# MORPH_RECONPLAT.net
KiCad netlist of a schematic drawn in EAGLE
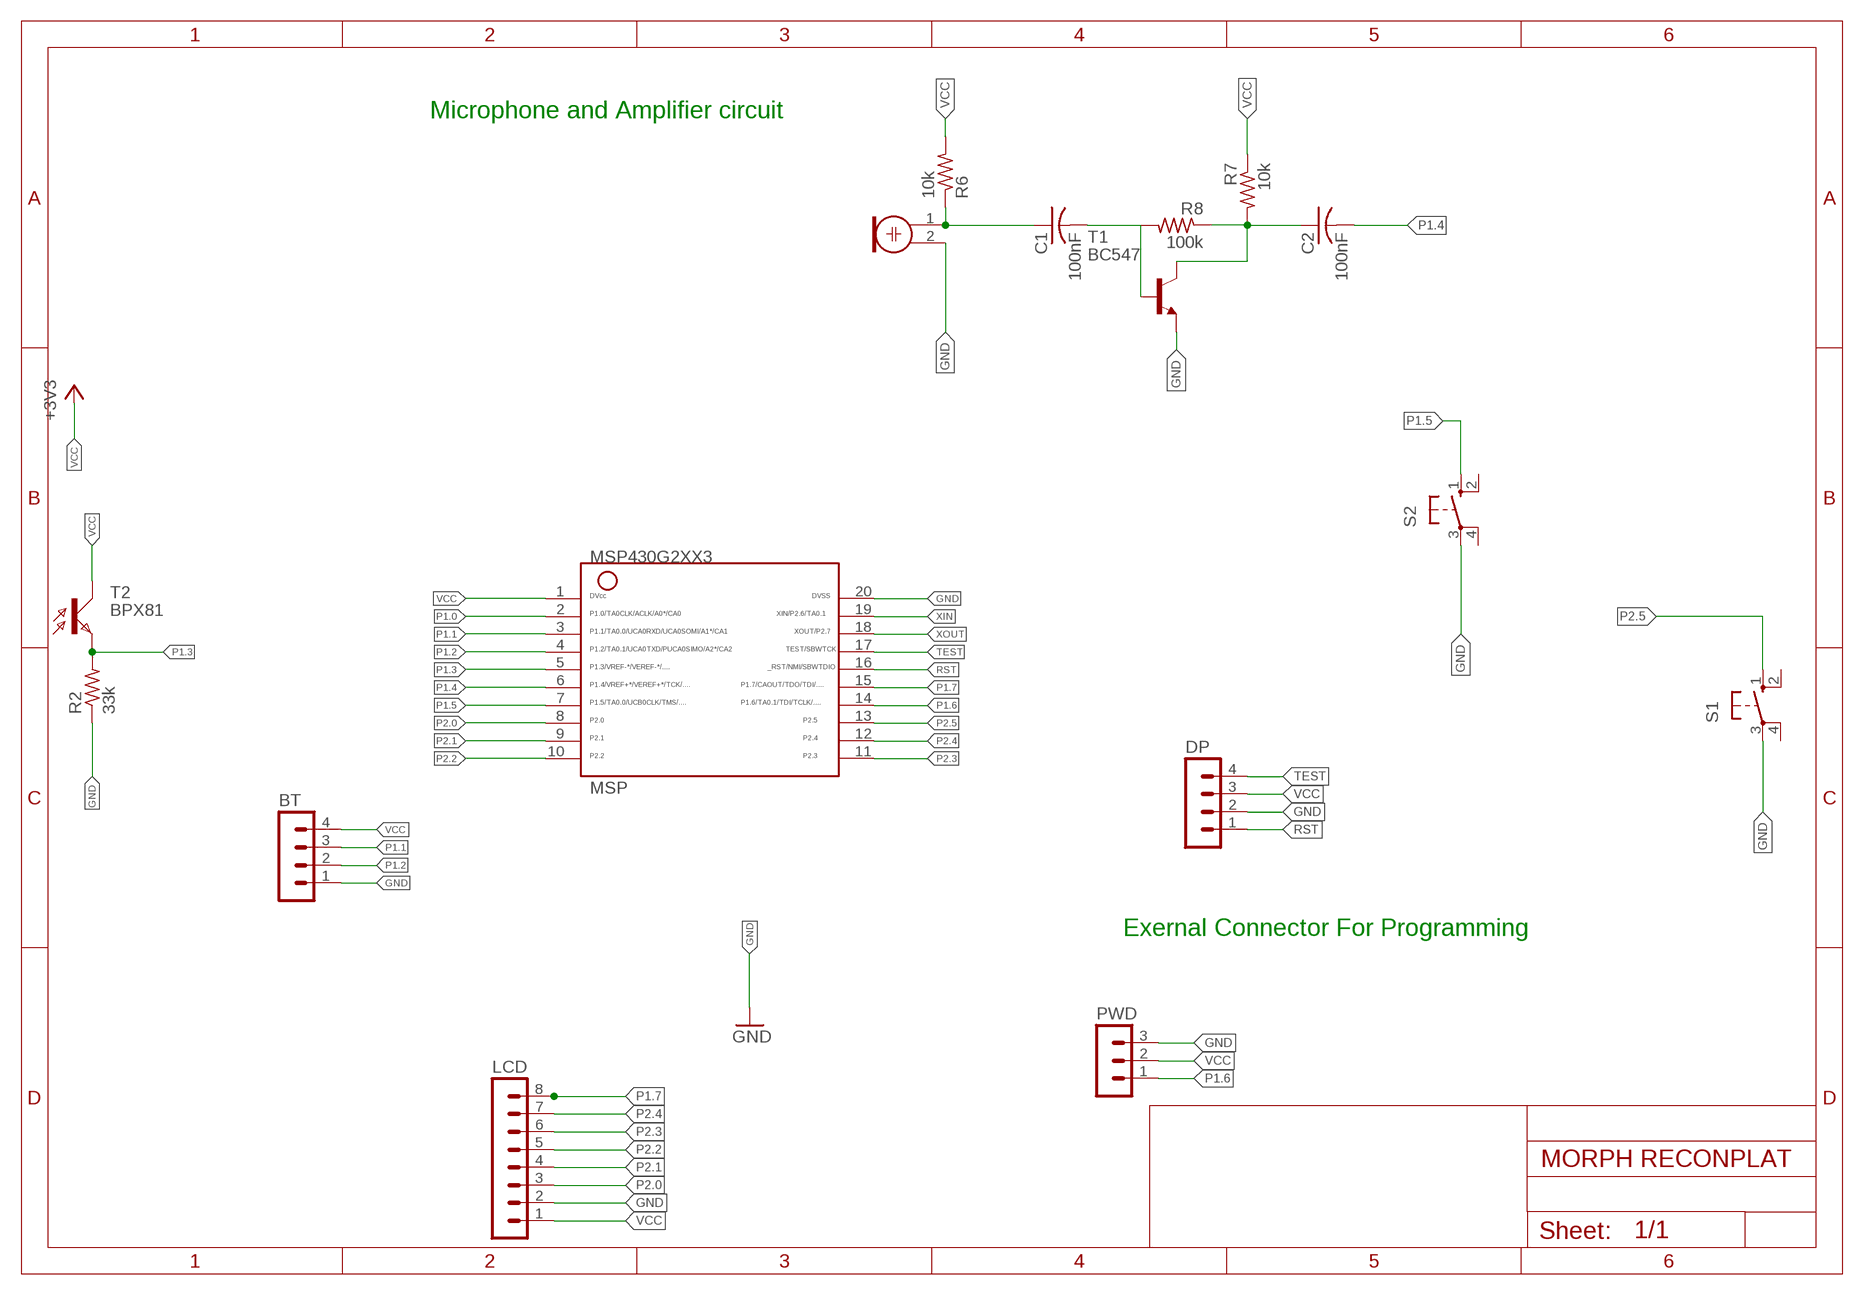
[diagram p0: schematic, sheet 1]

(export (version "E")
  (design (tool "Eeschema 10.0.6"))
  (components
    (comp (ref "BT")
      (value "MA04-1")
      (footprint "eagle-import:MA04-1")
      (libsource (lib "eagle-import") (part "MA04-1"))
    )
    (comp (ref "C1")
      (value "100nF")
      (footprint "eagle-import:C025-025X050")
      (libsource (lib "eagle-import") (part "C-US025-025X050"))
    )
    (comp (ref "C2")
      (value "100nF")
      (footprint "eagle-import:C025-025X050")
      (libsource (lib "eagle-import") (part "C-US025-025X050"))
    )
    (comp (ref "DP")
      (value "MA04-1")
      (footprint "eagle-import:MA04-1")
      (libsource (lib "eagle-import") (part "MA04-1"))
    )
    (comp (ref "LCD")
      (value "MA08-1")
      (footprint "eagle-import:MA08-1")
      (libsource (lib "eagle-import") (part "MA08-1"))
    )
    (comp (ref "M1")
      (value "ELECTRET_MICROPHON-WM-64PC/64PK")
      (footprint "eagle-import:WM-64PC_64PK")
      (libsource (lib "eagle-import") (part "ELECTRET_MICROPHON-WM-64PC/64PK"))
    )
    (comp (ref "MSP")
      (value "G2XX3---N20")
      (footprint "eagle-import:N20")
      (libsource (lib "eagle-import") (part "G2XX3---N20"))
    )
    (comp (ref "PWD")
      (value "MA03-1")
      (footprint "eagle-import:MA03-1")
      (libsource (lib "eagle-import") (part "MA03-1"))
    )
    (comp (ref "R2")
      (value "33k")
      (footprint "eagle-import:0207_10")
      (libsource (lib "eagle-import") (part "R-US_0207/10"))
    )
    (comp (ref "R6")
      (value "10k")
      (footprint "eagle-import:0207_10")
      (libsource (lib "eagle-import") (part "R-US_0207/10"))
    )
    (comp (ref "R7")
      (value "10k")
      (footprint "eagle-import:0207_10")
      (libsource (lib "eagle-import") (part "R-US_0207/10"))
    )
    (comp (ref "R8")
      (value "100k")
      (footprint "eagle-import:0207_10")
      (libsource (lib "eagle-import") (part "R-US_0207/10"))
    )
    (comp (ref "S1")
      (value "10-XX")
      (footprint "eagle-import:B3F-10XX")
      (fields (field (name "MPN") "B3F-1000"))
      (libsource (lib "eagle-import") (part "10-XX"))
    )
    (comp (ref "S2")
      (value "10-XX")
      (footprint "eagle-import:B3F-10XX")
      (fields (field (name "MPN") "B3F-1000"))
      (libsource (lib "eagle-import") (part "10-XX"))
    )
    (comp (ref "T1")
      (value "BC547")
      (footprint "eagle-import:TO92")
      (libsource (lib "eagle-import") (part "BC547"))
    )
    (comp (ref "T2")
      (value "BPX81")
      (footprint "eagle-import:BPX81")
      (libsource (lib "eagle-import") (part "BPX81"))
    )
  )
  (nets
    (net (code "1") (name "GND") (class "Default")
      (node (ref "BT") (pin "1") (pinfunction "1_1") (pintype "passive"))
      (node (ref "DP") (pin "2") (pinfunction "2_2") (pintype "passive"))
      (node (ref "LCD") (pin "2") (pinfunction "2_2") (pintype "passive"))
      (node (ref "M1") (pin "2") (pinfunction "2_2") (pintype "passive"))
      (node (ref "MSP") (pin "20") (pinfunction "20_20") (pintype "bidirectional"))
      (node (ref "PWD") (pin "3") (pinfunction "3_3") (pintype "passive"))
      (node (ref "R2") (pin "1") (pinfunction "1_1") (pintype "passive"))
      (node (ref "S1") (pin "3") (pinfunction "P_3") (pintype "passive"))
      (node (ref "S2") (pin "3") (pinfunction "P_3") (pintype "passive"))
      (node (ref "T1") (pin "1") (pinfunction "E_1") (pintype "passive"))
    )
    (net (code "2") (name "Net-(C1-Pad1)") (class "Default")
      (node (ref "C1") (pin "1") (pinfunction "1_1") (pintype "passive"))
      (node (ref "M1") (pin "1") (pinfunction "1_1") (pintype "passive"))
      (node (ref "R6") (pin "1") (pinfunction "1_1") (pintype "passive"))
    )
    (net (code "3") (name "Net-(T1-B)") (class "Default")
      (node (ref "C1") (pin "2") (pinfunction "2_2") (pintype "passive"))
      (node (ref "R8") (pin "2") (pinfunction "2_2") (pintype "passive"))
      (node (ref "T1") (pin "2") (pinfunction "B_2") (pintype "passive"))
    )
    (net (code "4") (name "Net-(T1-C)") (class "Default")
      (node (ref "C2") (pin "1") (pinfunction "1_1") (pintype "passive"))
      (node (ref "R7") (pin "2") (pinfunction "2_2") (pintype "passive"))
      (node (ref "R8") (pin "1") (pinfunction "1_1") (pintype "passive"))
      (node (ref "T1") (pin "3") (pinfunction "C_3") (pintype "passive"))
    )
    (net (code "5") (name "P1.0") (class "Default")
      (node (ref "MSP") (pin "2") (pinfunction "2_2") (pintype "bidirectional"))
    )
    (net (code "6") (name "P1.1") (class "Default")
      (node (ref "BT") (pin "3") (pinfunction "3_3") (pintype "passive"))
      (node (ref "MSP") (pin "3") (pinfunction "3_3") (pintype "bidirectional"))
    )
    (net (code "7") (name "P1.2") (class "Default")
      (node (ref "BT") (pin "2") (pinfunction "2_2") (pintype "passive"))
      (node (ref "MSP") (pin "4") (pinfunction "4_4") (pintype "bidirectional"))
    )
    (net (code "8") (name "P1.3") (class "Default")
      (node (ref "MSP") (pin "5") (pinfunction "5_5") (pintype "bidirectional"))
      (node (ref "R2") (pin "2") (pinfunction "2_2") (pintype "passive"))
      (node (ref "T2") (pin "E") (pinfunction "E_E") (pintype "passive"))
    )
    (net (code "9") (name "P1.4") (class "Default")
      (node (ref "C2") (pin "2") (pinfunction "2_2") (pintype "passive"))
      (node (ref "MSP") (pin "6") (pinfunction "6_6") (pintype "bidirectional"))
    )
    (net (code "10") (name "P1.5") (class "Default")
      (node (ref "MSP") (pin "7") (pinfunction "7_7") (pintype "bidirectional"))
      (node (ref "S2") (pin "1") (pinfunction "S_1") (pintype "passive"))
    )
    (net (code "11") (name "P1.6") (class "Default")
      (node (ref "MSP") (pin "14") (pinfunction "14_14") (pintype "bidirectional"))
      (node (ref "PWD") (pin "1") (pinfunction "1_1") (pintype "passive"))
    )
    (net (code "12") (name "P1.7") (class "Default")
      (node (ref "LCD") (pin "8") (pinfunction "8_8") (pintype "passive"))
      (node (ref "MSP") (pin "15") (pinfunction "15_15") (pintype "bidirectional"))
    )
    (net (code "13") (name "P2.0") (class "Default")
      (node (ref "LCD") (pin "3") (pinfunction "3_3") (pintype "passive"))
      (node (ref "MSP") (pin "8") (pinfunction "8_8") (pintype "bidirectional"))
    )
    (net (code "14") (name "P2.1") (class "Default")
      (node (ref "LCD") (pin "4") (pinfunction "4_4") (pintype "passive"))
      (node (ref "MSP") (pin "9") (pinfunction "9_9") (pintype "bidirectional"))
    )
    (net (code "15") (name "P2.2") (class "Default")
      (node (ref "LCD") (pin "5") (pinfunction "5_5") (pintype "passive"))
      (node (ref "MSP") (pin "10") (pinfunction "10_10") (pintype "bidirectional"))
    )
    (net (code "16") (name "P2.3") (class "Default")
      (node (ref "LCD") (pin "6") (pinfunction "6_6") (pintype "passive"))
      (node (ref "MSP") (pin "11") (pinfunction "11_11") (pintype "bidirectional"))
    )
    (net (code "17") (name "P2.4") (class "Default")
      (node (ref "LCD") (pin "7") (pinfunction "7_7") (pintype "passive"))
      (node (ref "MSP") (pin "12") (pinfunction "12_12") (pintype "bidirectional"))
    )
    (net (code "18") (name "P2.5") (class "Default")
      (node (ref "MSP") (pin "13") (pinfunction "13_13") (pintype "bidirectional"))
      (node (ref "S1") (pin "1") (pinfunction "S_1") (pintype "passive"))
    )
    (net (code "19") (name "RST") (class "Default")
      (node (ref "DP") (pin "1") (pinfunction "1_1") (pintype "passive"))
      (node (ref "MSP") (pin "16") (pinfunction "16_16") (pintype "bidirectional"))
    )
    (net (code "20") (name "TEST") (class "Default")
      (node (ref "DP") (pin "4") (pinfunction "4_4") (pintype "passive"))
      (node (ref "MSP") (pin "17") (pinfunction "17_17") (pintype "bidirectional"))
    )
    (net (code "21") (name "VCC") (class "Default")
      (node (ref "BT") (pin "4") (pinfunction "4_4") (pintype "passive"))
      (node (ref "DP") (pin "3") (pinfunction "3_3") (pintype "passive"))
      (node (ref "LCD") (pin "1") (pinfunction "1_1") (pintype "passive"))
      (node (ref "MSP") (pin "1") (pinfunction "1_1") (pintype "bidirectional"))
      (node (ref "PWD") (pin "2") (pinfunction "2_2") (pintype "passive"))
      (node (ref "R6") (pin "2") (pinfunction "2_2") (pintype "passive"))
      (node (ref "R7") (pin "1") (pinfunction "1_1") (pintype "passive"))
      (node (ref "T2") (pin "C") (pinfunction "C_C") (pintype "passive"))
    )
    (net (code "22") (name "XIN") (class "Default")
      (node (ref "MSP") (pin "19") (pinfunction "19_19") (pintype "bidirectional"))
    )
    (net (code "23") (name "XOUT") (class "Default")
      (node (ref "MSP") (pin "18") (pinfunction "18_18") (pintype "bidirectional"))
    )
    (net (code "24") (name "unconnected-(S1-P1-Pad4)") (class "Default")
      (node (ref "S1") (pin "4") (pinfunction "P1_4") (pintype "passive"))
    )
    (net (code "25") (name "unconnected-(S1-S1-Pad2)") (class "Default")
      (node (ref "S1") (pin "2") (pinfunction "S1_2") (pintype "passive"))
    )
    (net (code "26") (name "unconnected-(S2-P1-Pad4)") (class "Default")
      (node (ref "S2") (pin "4") (pinfunction "P1_4") (pintype "passive"))
    )
    (net (code "27") (name "unconnected-(S2-S1-Pad2)") (class "Default")
      (node (ref "S2") (pin "2") (pinfunction "S1_2") (pintype "passive"))
    )
  )
)
